# SCH_Naked_ATMega_2560_2021-08-20.net
KiCad netlist of a schematic drawn in EasyEDA
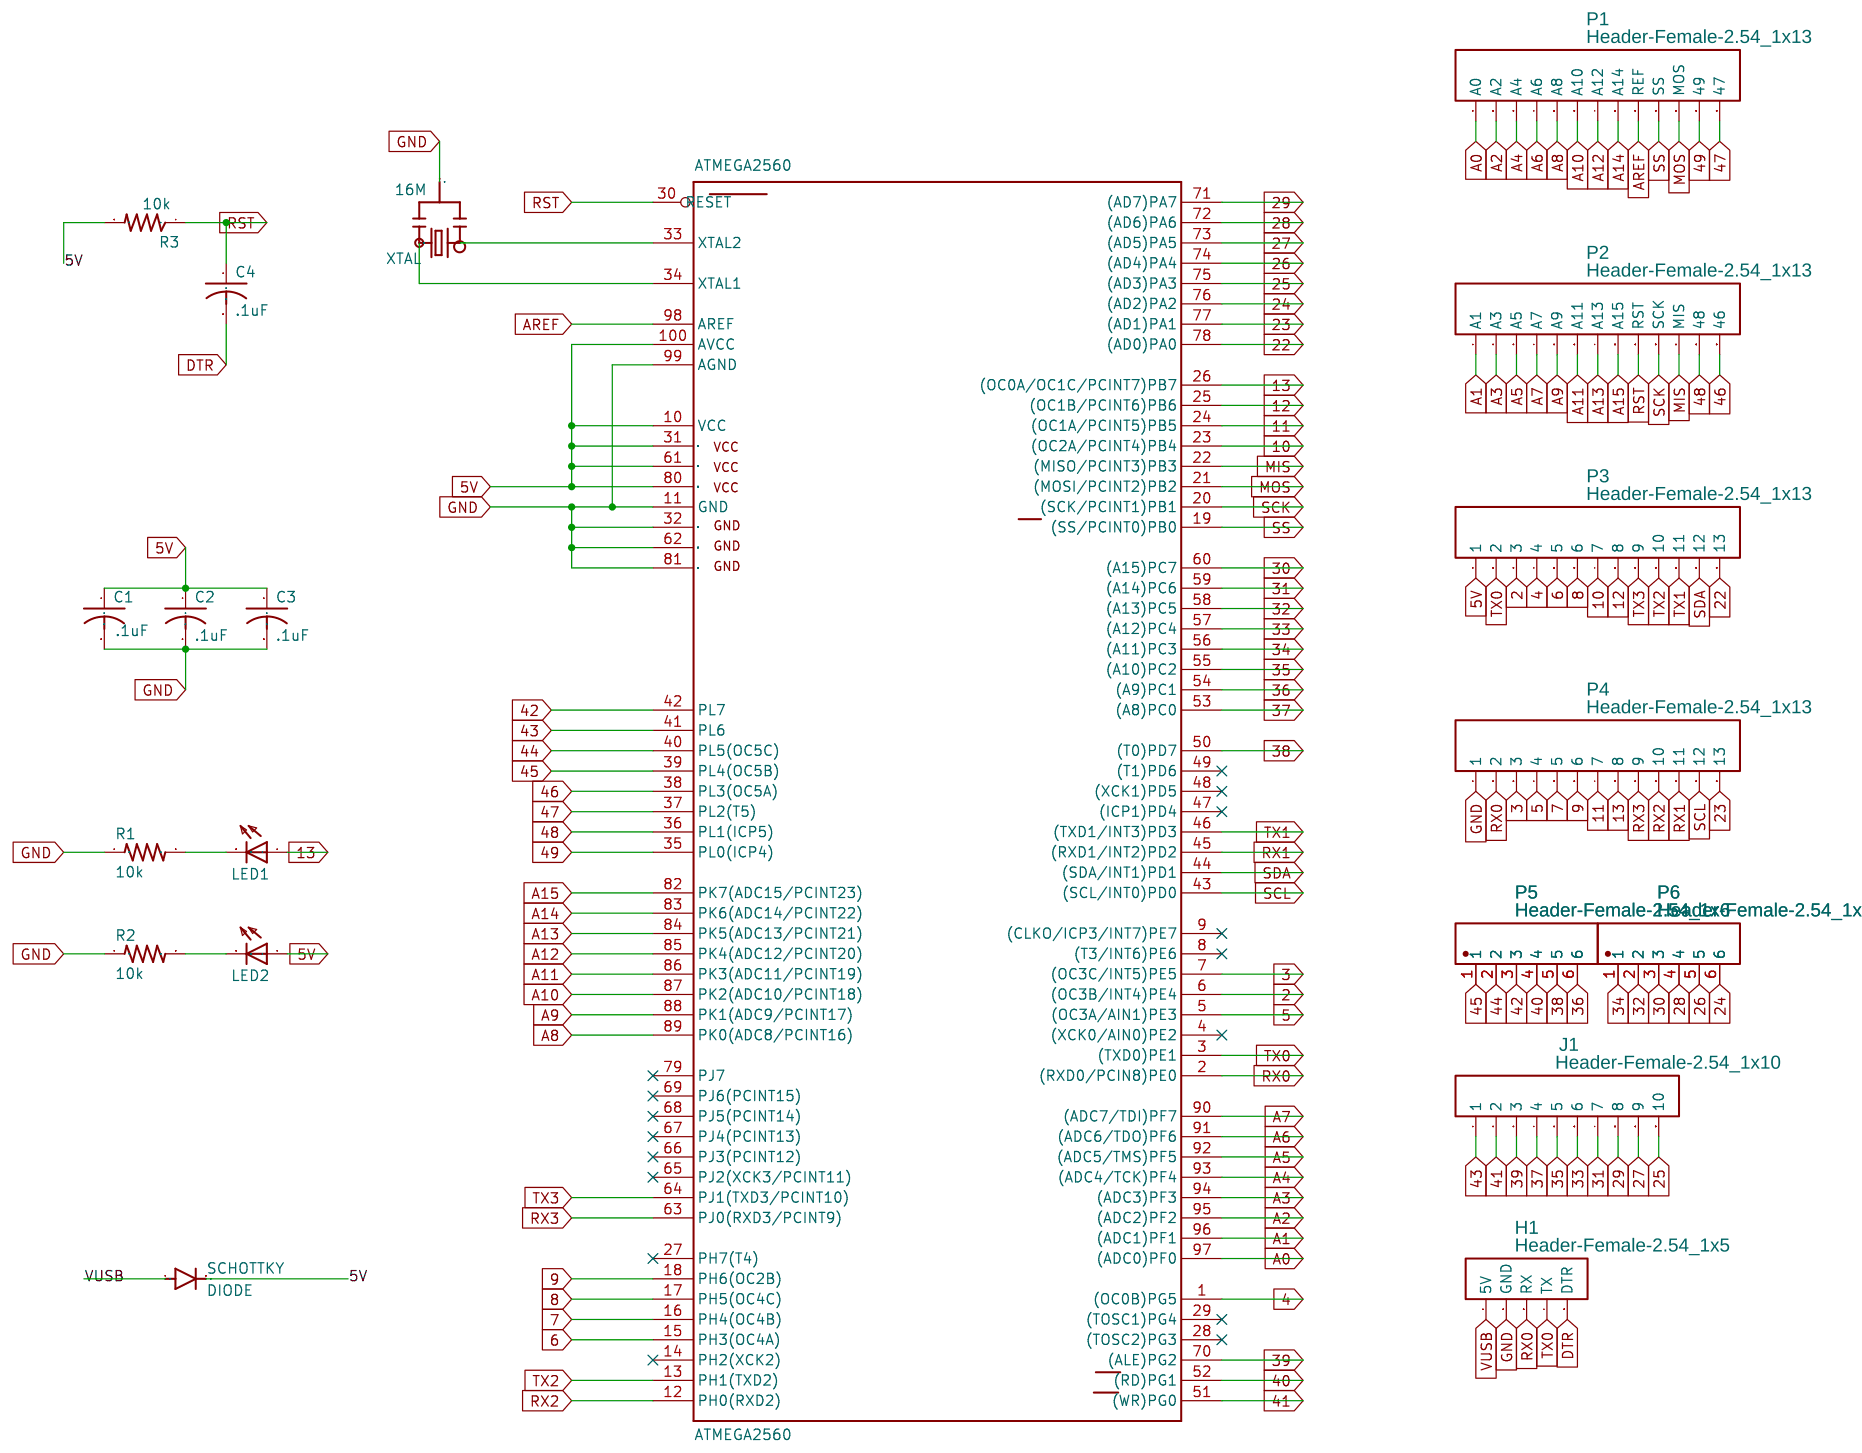
[diagram p0: schematic sheet]

(export (version "E")
  (design (tool "Eeschema 10.0.6"))
  (components
    (comp (ref "ATMEGA2560") (value "ATMEGA2560") (libsource (lib "") (part "Unknown_470_-340")))
    (comp (ref "C1") (value "CAPACITOR-SMD-0805") (libsource (lib "") (part "Unknown_60_-430")))
    (comp (ref "C2") (value ".1uF") (libsource (lib "") (part "Unknown_100_-430")))
    (comp (ref "C3") (value ".1uF") (libsource (lib "") (part "Unknown_140_-430")))
    (comp (ref "C4") (value ".1uF") (libsource (lib "") (part "Unknown_120_-590")))
    (comp (ref "H1")
      (value "Header-Female-2.54_1x5")
      (fields
        (field (name "BOM_Manufacturer Part") "2.54mm 1*5p Female header")
        (field (name "BOM_Supplier Part") "C50950")
      )
      (libsource (lib "") (part "Header-Female-2.54_1x5"))
    )
    (comp (ref "J1")
      (value "Header-Female-2.54_1x10")
      (fields
        (field (name "BOM_Manufacturer Part") "2.54mm 1*10P Straight Female header Gold-plated")
        (field (name "BOM_Supplier Part") "C35445")
      )
      (libsource (lib "") (part "Header-Female-2.54_1x10"))
    )
    (comp (ref "LED1") (value "L") (libsource (lib "") (part "Unknown_140_-310")))
    (comp (ref "LED2") (value "L") (libsource (lib "") (part "Unknown_140_-260")))
    (comp (ref "P1")
      (value "Header-Female-2.54_1x13")
      (fields
        (field (name "BOM_Manufacturer Part") "Female header 2.54-1*13P")
        (field (name "BOM_Supplier Part") "C52709")
      )
      (libsource (lib "") (part "Header-Female-2.54_1x13_1"))
    )
    (comp (ref "P2")
      (value "Header-Female-2.54_1x13")
      (fields
        (field (name "BOM_Manufacturer Part") "Female header 2.54-1*13P")
        (field (name "BOM_Supplier Part") "C52709")
      )
      (libsource (lib "") (part "Header-Female-2.54_1x13_2"))
    )
    (comp (ref "P3")
      (value "Header-Female-2.54_1x13")
      (fields
        (field (name "BOM_Manufacturer Part") "Female header 2.54-1*13P")
        (field (name "BOM_Supplier Part") "C52709")
      )
      (libsource (lib "") (part "Header-Female-2.54_1x13"))
    )
    (comp (ref "P4")
      (value "Header-Female-2.54_1x13")
      (fields
        (field (name "BOM_Manufacturer Part") "Female header 2.54-1*13P")
        (field (name "BOM_Supplier Part") "C52709")
      )
      (libsource (lib "") (part "Header-Female-2.54_1x13"))
    )
    (comp (ref "P5")
      (value "Header-Female-2.54_1x6")
      (fields
        (field (name "BOM_Manufacturer Part") "Female header 1*6p")
        (field (name "BOM_Supplier Part") "C40877")
      )
      (libsource (lib "") (part "Header-Female-2.54_1x6"))
    )
    (comp (ref "P6")
      (value "Header-Female-2.54_1x6")
      (fields
        (field (name "BOM_Manufacturer Part") "Female header 1*6p")
        (field (name "BOM_Supplier Part") "C40877")
      )
      (libsource (lib "") (part "Header-Female-2.54_1x6"))
    )
    (comp (ref "R1") (value "10k") (libsource (lib "") (part "Unknown_80_-310")))
    (comp (ref "R2") (value "10k") (libsource (lib "") (part "Unknown_80_-260")))
    (comp (ref "R3") (value "10k") (libsource (lib "") (part "Unknown_80_-620")))
    (comp (ref "SCHOTTKY") (value "DIODE") (libsource (lib "") (part "Unknown_100_-100")))
    (comp (ref "XTAL") (value "16M") (libsource (lib "") (part "Unknown_225_-620")))
  )
  (nets
    (net (code "1") (name "2") (class "Default")
      (node (ref "ATMEGA2560") (pin "6") (pinfunction "(OC3B/INT4)PE4_6") (pintype "bidirectional"))
      (node (ref "P3") (pin "3") (pinfunction "3_3") (pintype "input"))
    )
    (net (code "2") (name "3") (class "Default")
      (node (ref "ATMEGA2560") (pin "7") (pinfunction "(OC3C/INT5)PE5_7") (pintype "bidirectional"))
      (node (ref "P4") (pin "3") (pinfunction "3_3") (pintype "input"))
    )
    (net (code "3") (name "4") (class "Default")
      (node (ref "ATMEGA2560") (pin "1") (pinfunction "(OC0B)PG5_1") (pintype "bidirectional"))
      (node (ref "P3") (pin "4") (pinfunction "4_4") (pintype "input"))
    )
    (net (code "4") (name "5") (class "Default")
      (node (ref "ATMEGA2560") (pin "5") (pinfunction "(OC3A/AIN1)PE3_5") (pintype "bidirectional"))
      (node (ref "P4") (pin "4") (pinfunction "4_4") (pintype "input"))
    )
    (net (code "5") (name "5V") (class "Default")
      (node (ref "ATMEGA2560") (pin "10") (pinfunction "VCC_10") (pintype "bidirectional"))
      (node (ref "ATMEGA2560") (pin "100") (pinfunction "AVCC_100") (pintype "bidirectional"))
      (node (ref "ATMEGA2560") (pin "31") (pinfunction "VCC1_31") (pintype "bidirectional"))
      (node (ref "ATMEGA2560") (pin "61") (pinfunction "VCC2_61") (pintype "bidirectional"))
      (node (ref "ATMEGA2560") (pin "80") (pinfunction "VCC3_80") (pintype "bidirectional"))
      (node (ref "C1") (pin "1") (pinfunction "1_1") (pintype "bidirectional"))
      (node (ref "C2") (pin "1") (pinfunction "1_1") (pintype "bidirectional"))
      (node (ref "C3") (pin "1") (pinfunction "1_1") (pintype "bidirectional"))
      (node (ref "LED2") (pin "1") (pinfunction "A_1") (pintype "bidirectional"))
      (node (ref "P3") (pin "1") (pinfunction "1_1") (pintype "input"))
      (node (ref "R3") (pin "2") (pinfunction "2_2") (pintype "bidirectional"))
      (node (ref "SCHOTTKY") (pin "2") (pinfunction "C_2") (pintype "bidirectional"))
    )
    (net (code "6") (name "6") (class "Default")
      (node (ref "ATMEGA2560") (pin "15") (pinfunction "PH3(OC4A)_15") (pintype "bidirectional"))
      (node (ref "P3") (pin "5") (pinfunction "5_5") (pintype "input"))
    )
    (net (code "7") (name "7") (class "Default")
      (node (ref "ATMEGA2560") (pin "16") (pinfunction "PH4(OC4B)_16") (pintype "bidirectional"))
      (node (ref "P4") (pin "5") (pinfunction "5_5") (pintype "input"))
    )
    (net (code "8") (name "8") (class "Default")
      (node (ref "ATMEGA2560") (pin "17") (pinfunction "PH5(OC4C)_17") (pintype "bidirectional"))
      (node (ref "P3") (pin "6") (pinfunction "6_6") (pintype "input"))
    )
    (net (code "9") (name "9") (class "Default")
      (node (ref "ATMEGA2560") (pin "18") (pinfunction "PH6(OC2B)_18") (pintype "bidirectional"))
      (node (ref "P4") (pin "6") (pinfunction "6_6") (pintype "input"))
    )
    (net (code "10") (name "10") (class "Default")
      (node (ref "ATMEGA2560") (pin "23") (pinfunction "(OC2A/PCINT4)PB4_23") (pintype "bidirectional"))
      (node (ref "P3") (pin "7") (pinfunction "7_7") (pintype "input"))
    )
    (net (code "11") (name "11") (class "Default")
      (node (ref "ATMEGA2560") (pin "24") (pinfunction "(OC1A/PCINT5)PB5_24") (pintype "bidirectional"))
      (node (ref "P4") (pin "7") (pinfunction "7_7") (pintype "input"))
    )
    (net (code "12") (name "12") (class "Default")
      (node (ref "ATMEGA2560") (pin "25") (pinfunction "(OC1B/PCINT6)PB6_25") (pintype "bidirectional"))
      (node (ref "P3") (pin "8") (pinfunction "8_8") (pintype "input"))
    )
    (net (code "13") (name "13") (class "Default")
      (node (ref "ATMEGA2560") (pin "26") (pinfunction "(OC0A/OC1C/PCINT7)PB7_26") (pintype "bidirectional"))
      (node (ref "LED1") (pin "1") (pinfunction "A_1") (pintype "bidirectional"))
      (node (ref "P4") (pin "8") (pinfunction "8_8") (pintype "input"))
    )
    (net (code "14") (name "22") (class "Default")
      (node (ref "ATMEGA2560") (pin "78") (pinfunction "(AD0)PA0_78") (pintype "bidirectional"))
      (node (ref "P3") (pin "13") (pinfunction "13_13") (pintype "input"))
    )
    (net (code "15") (name "23") (class "Default")
      (node (ref "ATMEGA2560") (pin "77") (pinfunction "(AD1)PA1_77") (pintype "bidirectional"))
      (node (ref "P4") (pin "13") (pinfunction "13_13") (pintype "input"))
    )
    (net (code "16") (name "24") (class "Default")
      (node (ref "ATMEGA2560") (pin "76") (pinfunction "(AD2)PA2_76") (pintype "bidirectional"))
      (node (ref "P6") (pin "6") (pinfunction "6_6") (pintype "unspecified"))
    )
    (net (code "17") (name "25") (class "Default")
      (node (ref "ATMEGA2560") (pin "75") (pinfunction "(AD3)PA3_75") (pintype "bidirectional"))
      (node (ref "J1") (pin "10") (pinfunction "10_10") (pintype "input"))
    )
    (net (code "18") (name "26") (class "Default")
      (node (ref "ATMEGA2560") (pin "74") (pinfunction "(AD4)PA4_74") (pintype "bidirectional"))
      (node (ref "P6") (pin "5") (pinfunction "5_5") (pintype "unspecified"))
    )
    (net (code "19") (name "27") (class "Default")
      (node (ref "ATMEGA2560") (pin "73") (pinfunction "(AD5)PA5_73") (pintype "bidirectional"))
      (node (ref "J1") (pin "9") (pinfunction "9_9") (pintype "input"))
    )
    (net (code "20") (name "28") (class "Default")
      (node (ref "ATMEGA2560") (pin "72") (pinfunction "(AD6)PA6_72") (pintype "bidirectional"))
      (node (ref "P6") (pin "4") (pinfunction "4_4") (pintype "unspecified"))
    )
    (net (code "21") (name "29") (class "Default")
      (node (ref "ATMEGA2560") (pin "71") (pinfunction "(AD7)PA7_71") (pintype "bidirectional"))
      (node (ref "J1") (pin "8") (pinfunction "8_8") (pintype "input"))
    )
    (net (code "22") (name "30") (class "Default")
      (node (ref "ATMEGA2560") (pin "60") (pinfunction "(A15)PC7_60") (pintype "bidirectional"))
      (node (ref "P6") (pin "3") (pinfunction "3_3") (pintype "unspecified"))
    )
    (net (code "23") (name "31") (class "Default")
      (node (ref "ATMEGA2560") (pin "59") (pinfunction "(A14)PC6_59") (pintype "bidirectional"))
      (node (ref "J1") (pin "7") (pinfunction "7_7") (pintype "input"))
    )
    (net (code "24") (name "32") (class "Default")
      (node (ref "ATMEGA2560") (pin "58") (pinfunction "(A13)PC5_58") (pintype "bidirectional"))
      (node (ref "P6") (pin "2") (pinfunction "2_2") (pintype "unspecified"))
    )
    (net (code "25") (name "33") (class "Default")
      (node (ref "ATMEGA2560") (pin "57") (pinfunction "(A12)PC4_57") (pintype "bidirectional"))
      (node (ref "J1") (pin "6") (pinfunction "6_6") (pintype "input"))
    )
    (net (code "26") (name "34") (class "Default")
      (node (ref "ATMEGA2560") (pin "56") (pinfunction "(A11)PC3_56") (pintype "bidirectional"))
      (node (ref "P6") (pin "1") (pinfunction "1_1") (pintype "unspecified"))
    )
    (net (code "27") (name "35") (class "Default")
      (node (ref "ATMEGA2560") (pin "55") (pinfunction "(A10)PC2_55") (pintype "bidirectional"))
      (node (ref "J1") (pin "5") (pinfunction "5_5") (pintype "input"))
    )
    (net (code "28") (name "36") (class "Default")
      (node (ref "ATMEGA2560") (pin "54") (pinfunction "(A9)PC1_54") (pintype "bidirectional"))
      (node (ref "P5") (pin "6") (pinfunction "6_6") (pintype "unspecified"))
    )
    (net (code "29") (name "37") (class "Default")
      (node (ref "ATMEGA2560") (pin "53") (pinfunction "(A8)PC0_53") (pintype "bidirectional"))
      (node (ref "J1") (pin "4") (pinfunction "4_4") (pintype "input"))
    )
    (net (code "30") (name "38") (class "Default")
      (node (ref "ATMEGA2560") (pin "50") (pinfunction "(T0)PD7_50") (pintype "bidirectional"))
      (node (ref "P5") (pin "5") (pinfunction "5_5") (pintype "unspecified"))
    )
    (net (code "31") (name "39") (class "Default")
      (node (ref "ATMEGA2560") (pin "70") (pinfunction "(ALE)PG2_70") (pintype "bidirectional"))
      (node (ref "J1") (pin "3") (pinfunction "3_3") (pintype "input"))
    )
    (net (code "32") (name "40") (class "Default")
      (node (ref "ATMEGA2560") (pin "52") (pinfunction "(RD)PG1_52") (pintype "bidirectional"))
      (node (ref "P5") (pin "4") (pinfunction "4_4") (pintype "unspecified"))
    )
    (net (code "33") (name "41") (class "Default")
      (node (ref "ATMEGA2560") (pin "51") (pinfunction "(WR)PG0_51") (pintype "bidirectional"))
      (node (ref "J1") (pin "2") (pinfunction "2_2") (pintype "input"))
    )
    (net (code "34") (name "42") (class "Default")
      (node (ref "ATMEGA2560") (pin "42") (pinfunction "PL7_42") (pintype "bidirectional"))
      (node (ref "P5") (pin "3") (pinfunction "3_3") (pintype "unspecified"))
    )
    (net (code "35") (name "43") (class "Default")
      (node (ref "ATMEGA2560") (pin "41") (pinfunction "PL6_41") (pintype "bidirectional"))
      (node (ref "J1") (pin "1") (pinfunction "1_1") (pintype "input"))
    )
    (net (code "36") (name "44") (class "Default")
      (node (ref "ATMEGA2560") (pin "40") (pinfunction "PL5(OC5C)_40") (pintype "bidirectional"))
      (node (ref "P5") (pin "2") (pinfunction "2_2") (pintype "unspecified"))
    )
    (net (code "37") (name "45") (class "Default")
      (node (ref "ATMEGA2560") (pin "39") (pinfunction "PL4(OC5B)_39") (pintype "bidirectional"))
      (node (ref "P5") (pin "1") (pinfunction "1_1") (pintype "unspecified"))
    )
    (net (code "38") (name "46") (class "Default")
      (node (ref "ATMEGA2560") (pin "38") (pinfunction "PL3(OC5A)_38") (pintype "bidirectional"))
      (node (ref "P2") (pin "13") (pinfunction "46_13") (pintype "input"))
    )
    (net (code "39") (name "47") (class "Default")
      (node (ref "ATMEGA2560") (pin "37") (pinfunction "PL2(T5)_37") (pintype "bidirectional"))
      (node (ref "P1") (pin "13") (pinfunction "47_13") (pintype "input"))
    )
    (net (code "40") (name "48") (class "Default")
      (node (ref "ATMEGA2560") (pin "36") (pinfunction "PL1(ICP5)_36") (pintype "bidirectional"))
      (node (ref "P2") (pin "12") (pinfunction "48_12") (pintype "input"))
    )
    (net (code "41") (name "49") (class "Default")
      (node (ref "ATMEGA2560") (pin "35") (pinfunction "PL0(ICP4)_35") (pintype "bidirectional"))
      (node (ref "P1") (pin "12") (pinfunction "49_12") (pintype "input"))
    )
    (net (code "42") (name "A0") (class "Default")
      (node (ref "ATMEGA2560") (pin "97") (pinfunction "(ADC0)PF0_97") (pintype "bidirectional"))
      (node (ref "P1") (pin "1") (pinfunction "A0_1") (pintype "input"))
    )
    (net (code "43") (name "A1") (class "Default")
      (node (ref "ATMEGA2560") (pin "96") (pinfunction "(ADC1)PF1_96") (pintype "bidirectional"))
      (node (ref "P2") (pin "1") (pinfunction "A1_1") (pintype "input"))
    )
    (net (code "44") (name "A2") (class "Default")
      (node (ref "ATMEGA2560") (pin "95") (pinfunction "(ADC2)PF2_95") (pintype "bidirectional"))
      (node (ref "P1") (pin "2") (pinfunction "A2_2") (pintype "input"))
    )
    (net (code "45") (name "A3") (class "Default")
      (node (ref "ATMEGA2560") (pin "94") (pinfunction "(ADC3)PF3_94") (pintype "bidirectional"))
      (node (ref "P2") (pin "2") (pinfunction "A3_2") (pintype "input"))
    )
    (net (code "46") (name "A4") (class "Default")
      (node (ref "ATMEGA2560") (pin "93") (pinfunction "(ADC4/TCK)PF4_93") (pintype "bidirectional"))
      (node (ref "P1") (pin "3") (pinfunction "A4_3") (pintype "input"))
    )
    (net (code "47") (name "A5") (class "Default")
      (node (ref "ATMEGA2560") (pin "92") (pinfunction "(ADC5/TMS)PF5_92") (pintype "bidirectional"))
      (node (ref "P2") (pin "3") (pinfunction "A5_3") (pintype "input"))
    )
    (net (code "48") (name "A6") (class "Default")
      (node (ref "ATMEGA2560") (pin "91") (pinfunction "(ADC6/TDO)PF6_91") (pintype "bidirectional"))
      (node (ref "P1") (pin "4") (pinfunction "A6_4") (pintype "input"))
    )
    (net (code "49") (name "A7") (class "Default")
      (node (ref "ATMEGA2560") (pin "90") (pinfunction "(ADC7/TDI)PF7_90") (pintype "bidirectional"))
      (node (ref "P2") (pin "4") (pinfunction "A7_4") (pintype "input"))
    )
    (net (code "50") (name "A8") (class "Default")
      (node (ref "ATMEGA2560") (pin "89") (pinfunction "PK0(ADC8/PCINT16)_89") (pintype "bidirectional"))
      (node (ref "P1") (pin "5") (pinfunction "A8_5") (pintype "input"))
    )
    (net (code "51") (name "A9") (class "Default")
      (node (ref "ATMEGA2560") (pin "88") (pinfunction "PK1(ADC9/PCINT17)_88") (pintype "bidirectional"))
      (node (ref "P2") (pin "5") (pinfunction "A9_5") (pintype "input"))
    )
    (net (code "52") (name "A10") (class "Default")
      (node (ref "ATMEGA2560") (pin "87") (pinfunction "PK2(ADC10/PCINT18)_87") (pintype "bidirectional"))
      (node (ref "P1") (pin "6") (pinfunction "A10_6") (pintype "input"))
    )
    (net (code "53") (name "A11") (class "Default")
      (node (ref "ATMEGA2560") (pin "86") (pinfunction "PK3(ADC11/PCINT19)_86") (pintype "bidirectional"))
      (node (ref "P2") (pin "6") (pinfunction "A11_6") (pintype "input"))
    )
    (net (code "54") (name "A12") (class "Default")
      (node (ref "ATMEGA2560") (pin "85") (pinfunction "PK4(ADC12/PCINT20)_85") (pintype "bidirectional"))
      (node (ref "P1") (pin "7") (pinfunction "A12_7") (pintype "input"))
    )
    (net (code "55") (name "A13") (class "Default")
      (node (ref "ATMEGA2560") (pin "84") (pinfunction "PK5(ADC13/PCINT21)_84") (pintype "bidirectional"))
      (node (ref "P2") (pin "7") (pinfunction "A13_7") (pintype "input"))
    )
    (net (code "56") (name "A14") (class "Default")
      (node (ref "ATMEGA2560") (pin "83") (pinfunction "PK6(ADC14/PCINT22)_83") (pintype "bidirectional"))
      (node (ref "P1") (pin "8") (pinfunction "A14_8") (pintype "input"))
    )
    (net (code "57") (name "A15") (class "Default")
      (node (ref "ATMEGA2560") (pin "82") (pinfunction "PK7(ADC15/PCINT23)_82") (pintype "bidirectional"))
      (node (ref "P2") (pin "8") (pinfunction "A15_8") (pintype "input"))
    )
    (net (code "58") (name "AREF") (class "Default")
      (node (ref "ATMEGA2560") (pin "98") (pinfunction "AREF_98") (pintype "bidirectional"))
      (node (ref "P1") (pin "9") (pinfunction "REF_9") (pintype "input"))
    )
    (net (code "59") (name "DTR") (class "Default")
      (node (ref "C4") (pin "2") (pinfunction "2_2") (pintype "bidirectional"))
      (node (ref "H1") (pin "5") (pinfunction "DTR_5") (pintype "input"))
    )
    (net (code "60") (name "GND") (class "Default")
      (node (ref "ATMEGA2560") (pin "11") (pinfunction "GND_11") (pintype "bidirectional"))
      (node (ref "ATMEGA2560") (pin "32") (pinfunction "GND1_32") (pintype "bidirectional"))
      (node (ref "ATMEGA2560") (pin "62") (pinfunction "GND2_62") (pintype "bidirectional"))
      (node (ref "ATMEGA2560") (pin "81") (pinfunction "GND3_81") (pintype "bidirectional"))
      (node (ref "ATMEGA2560") (pin "99") (pinfunction "AGND_99") (pintype "bidirectional"))
      (node (ref "C1") (pin "2") (pinfunction "2_2") (pintype "bidirectional"))
      (node (ref "C2") (pin "2") (pinfunction "2_2") (pintype "bidirectional"))
      (node (ref "C3") (pin "2") (pinfunction "2_2") (pintype "bidirectional"))
      (node (ref "H1") (pin "2") (pinfunction "GND_2") (pintype "input"))
      (node (ref "P4") (pin "1") (pinfunction "1_1") (pintype "input"))
      (node (ref "R1") (pin "1") (pinfunction "1_1") (pintype "bidirectional"))
      (node (ref "R2") (pin "1") (pinfunction "1_1") (pintype "bidirectional"))
      (node (ref "XTAL") (pin "2") (pinfunction "2_2") (pintype "bidirectional"))
    )
    (net (code "61") (name "MIS") (class "Default")
      (node (ref "ATMEGA2560") (pin "22") (pinfunction "(MISO/PCINT3)PB3_22") (pintype "bidirectional"))
      (node (ref "P2") (pin "11") (pinfunction "MIS_11") (pintype "input"))
    )
    (net (code "62") (name "MOS") (class "Default")
      (node (ref "ATMEGA2560") (pin "21") (pinfunction "(MOSI/PCINT2)PB2_21") (pintype "bidirectional"))
      (node (ref "P1") (pin "11") (pinfunction "MOS_11") (pintype "input"))
    )
    (net (code "63") (name "Net-(ATMEGA2560-XTAL1)") (class "Default")
      (node (ref "ATMEGA2560") (pin "34") (pinfunction "XTAL1_34") (pintype "bidirectional"))
      (node (ref "XTAL") (pin "3") (pinfunction "3_3") (pintype "bidirectional"))
    )
    (net (code "64") (name "Net-(ATMEGA2560-XTAL2)") (class "Default")
      (node (ref "ATMEGA2560") (pin "33") (pinfunction "XTAL2_33") (pintype "bidirectional"))
      (node (ref "XTAL") (pin "1") (pinfunction "1_1") (pintype "bidirectional"))
    )
    (net (code "65") (name "Net-(LED1-C)") (class "Default")
      (node (ref "LED1") (pin "2") (pinfunction "C_2") (pintype "bidirectional"))
      (node (ref "R1") (pin "2") (pinfunction "2_2") (pintype "bidirectional"))
    )
    (net (code "66") (name "Net-(LED2-C)") (class "Default")
      (node (ref "LED2") (pin "2") (pinfunction "C_2") (pintype "bidirectional"))
      (node (ref "R2") (pin "2") (pinfunction "2_2") (pintype "bidirectional"))
    )
    (net (code "67") (name "RST") (class "Default")
      (node (ref "ATMEGA2560") (pin "30") (pinfunction "RESET_30") (pintype "bidirectional"))
      (node (ref "C4") (pin "1") (pinfunction "1_1") (pintype "bidirectional"))
      (node (ref "P2") (pin "9") (pinfunction "RST_9") (pintype "input"))
      (node (ref "R3") (pin "1") (pinfunction "1_1") (pintype "bidirectional"))
    )
    (net (code "68") (name "RX0") (class "Default")
      (node (ref "ATMEGA2560") (pin "2") (pinfunction "(RXD0/PCIN8)PE0_2") (pintype "bidirectional"))
      (node (ref "H1") (pin "3") (pinfunction "RX_3") (pintype "input"))
      (node (ref "P4") (pin "2") (pinfunction "2_2") (pintype "input"))
    )
    (net (code "69") (name "RX1") (class "Default")
      (node (ref "ATMEGA2560") (pin "45") (pinfunction "(RXD1/INT2)PD2_45") (pintype "bidirectional"))
      (node (ref "P4") (pin "11") (pinfunction "11_11") (pintype "input"))
    )
    (net (code "70") (name "RX2") (class "Default")
      (node (ref "ATMEGA2560") (pin "12") (pinfunction "PH0(RXD2)_12") (pintype "bidirectional"))
      (node (ref "P4") (pin "10") (pinfunction "10_10") (pintype "input"))
    )
    (net (code "71") (name "RX3") (class "Default")
      (node (ref "ATMEGA2560") (pin "63") (pinfunction "PJ0(RXD3/PCINT9)_63") (pintype "bidirectional"))
      (node (ref "P4") (pin "9") (pinfunction "9_9") (pintype "input"))
    )
    (net (code "72") (name "SCK") (class "Default")
      (node (ref "ATMEGA2560") (pin "20") (pinfunction "(SCK/PCINT1)PB1_20") (pintype "bidirectional"))
      (node (ref "P2") (pin "10") (pinfunction "SCK_10") (pintype "input"))
    )
    (net (code "73") (name "SCL") (class "Default")
      (node (ref "ATMEGA2560") (pin "43") (pinfunction "(SCL/INT0)PD0_43") (pintype "bidirectional"))
      (node (ref "P4") (pin "12") (pinfunction "12_12") (pintype "input"))
    )
    (net (code "74") (name "SDA") (class "Default")
      (node (ref "ATMEGA2560") (pin "44") (pinfunction "(SDA/INT1)PD1_44") (pintype "bidirectional"))
      (node (ref "P3") (pin "12") (pinfunction "12_12") (pintype "input"))
    )
    (net (code "75") (name "SS") (class "Default")
      (node (ref "ATMEGA2560") (pin "19") (pinfunction "(SS/PCINT0)PB0_19") (pintype "bidirectional"))
      (node (ref "P1") (pin "10") (pinfunction "SS_10") (pintype "input"))
    )
    (net (code "76") (name "TX0") (class "Default")
      (node (ref "ATMEGA2560") (pin "3") (pinfunction "(TXD0)PE1_3") (pintype "bidirectional"))
      (node (ref "H1") (pin "4") (pinfunction "TX_4") (pintype "input"))
      (node (ref "P3") (pin "2") (pinfunction "2_2") (pintype "input"))
    )
    (net (code "77") (name "TX1") (class "Default")
      (node (ref "ATMEGA2560") (pin "46") (pinfunction "(TXD1/INT3)PD3_46") (pintype "bidirectional"))
      (node (ref "P3") (pin "11") (pinfunction "11_11") (pintype "input"))
    )
    (net (code "78") (name "TX2") (class "Default")
      (node (ref "ATMEGA2560") (pin "13") (pinfunction "PH1(TXD2)_13") (pintype "bidirectional"))
      (node (ref "P3") (pin "10") (pinfunction "10_10") (pintype "input"))
    )
    (net (code "79") (name "TX3") (class "Default")
      (node (ref "ATMEGA2560") (pin "64") (pinfunction "PJ1(TXD3/PCINT10)_64") (pintype "bidirectional"))
      (node (ref "P3") (pin "9") (pinfunction "9_9") (pintype "input"))
    )
    (net (code "80") (name "VUSB") (class "Default")
      (node (ref "H1") (pin "1") (pinfunction "5V_1") (pintype "input"))
      (node (ref "SCHOTTKY") (pin "1") (pinfunction "A_1") (pintype "bidirectional"))
    )
    (net (code "81") (name "unconnected-(ATMEGA2560-(CLKO{slash}ICP3{slash}INT7)PE7-Pad9)") (class "Default")
      (node (ref "ATMEGA2560") (pin "9") (pinfunction "(CLKO/ICP3/INT7)PE7_9") (pintype "bidirectional+no_connect"))
    )
    (net (code "82") (name "unconnected-(ATMEGA2560-(ICP1)PD4-Pad47)") (class "Default")
      (node (ref "ATMEGA2560") (pin "47") (pinfunction "(ICP1)PD4_47") (pintype "bidirectional+no_connect"))
    )
    (net (code "83") (name "unconnected-(ATMEGA2560-(T1)PD6-Pad49)") (class "Default")
      (node (ref "ATMEGA2560") (pin "49") (pinfunction "(T1)PD6_49") (pintype "bidirectional+no_connect"))
    )
    (net (code "84") (name "unconnected-(ATMEGA2560-(T3{slash}INT6)PE6-Pad8)") (class "Default")
      (node (ref "ATMEGA2560") (pin "8") (pinfunction "(T3/INT6)PE6_8") (pintype "bidirectional+no_connect"))
    )
    (net (code "85") (name "unconnected-(ATMEGA2560-(TOSC1)PG4-Pad29)") (class "Default")
      (node (ref "ATMEGA2560") (pin "29") (pinfunction "(TOSC1)PG4_29") (pintype "bidirectional+no_connect"))
    )
    (net (code "86") (name "unconnected-(ATMEGA2560-(TOSC2)PG3-Pad28)") (class "Default")
      (node (ref "ATMEGA2560") (pin "28") (pinfunction "(TOSC2)PG3_28") (pintype "bidirectional+no_connect"))
    )
    (net (code "87") (name "unconnected-(ATMEGA2560-(XCK0{slash}AIN0)PE2-Pad4)") (class "Default")
      (node (ref "ATMEGA2560") (pin "4") (pinfunction "(XCK0/AIN0)PE2_4") (pintype "bidirectional+no_connect"))
    )
    (net (code "88") (name "unconnected-(ATMEGA2560-(XCK1)PD5-Pad48)") (class "Default")
      (node (ref "ATMEGA2560") (pin "48") (pinfunction "(XCK1)PD5_48") (pintype "bidirectional+no_connect"))
    )
    (net (code "89") (name "unconnected-(ATMEGA2560-PH2(XCK2)-Pad14)") (class "Default")
      (node (ref "ATMEGA2560") (pin "14") (pinfunction "PH2(XCK2)_14") (pintype "bidirectional+no_connect"))
    )
    (net (code "90") (name "unconnected-(ATMEGA2560-PH7(T4)-Pad27)") (class "Default")
      (node (ref "ATMEGA2560") (pin "27") (pinfunction "PH7(T4)_27") (pintype "bidirectional+no_connect"))
    )
    (net (code "91") (name "unconnected-(ATMEGA2560-PJ2(XCK3{slash}PCINT11)-Pad65)") (class "Default")
      (node (ref "ATMEGA2560") (pin "65") (pinfunction "PJ2(XCK3/PCINT11)_65") (pintype "bidirectional+no_connect"))
    )
    (net (code "92") (name "unconnected-(ATMEGA2560-PJ3(PCINT12)-Pad66)") (class "Default")
      (node (ref "ATMEGA2560") (pin "66") (pinfunction "PJ3(PCINT12)_66") (pintype "bidirectional+no_connect"))
    )
    (net (code "93") (name "unconnected-(ATMEGA2560-PJ4(PCINT13)-Pad67)") (class "Default")
      (node (ref "ATMEGA2560") (pin "67") (pinfunction "PJ4(PCINT13)_67") (pintype "bidirectional+no_connect"))
    )
    (net (code "94") (name "unconnected-(ATMEGA2560-PJ5(PCINT14)-Pad68)") (class "Default")
      (node (ref "ATMEGA2560") (pin "68") (pinfunction "PJ5(PCINT14)_68") (pintype "bidirectional+no_connect"))
    )
    (net (code "95") (name "unconnected-(ATMEGA2560-PJ6(PCINT15)-Pad69)") (class "Default")
      (node (ref "ATMEGA2560") (pin "69") (pinfunction "PJ6(PCINT15)_69") (pintype "bidirectional+no_connect"))
    )
    (net (code "96") (name "unconnected-(ATMEGA2560-PJ7-Pad79)") (class "Default")
      (node (ref "ATMEGA2560") (pin "79") (pinfunction "PJ7_79") (pintype "bidirectional+no_connect"))
    )
  )
)
